# 1_PowerSupply.net
KiCad netlist of a schematic drawn in Altium Designer
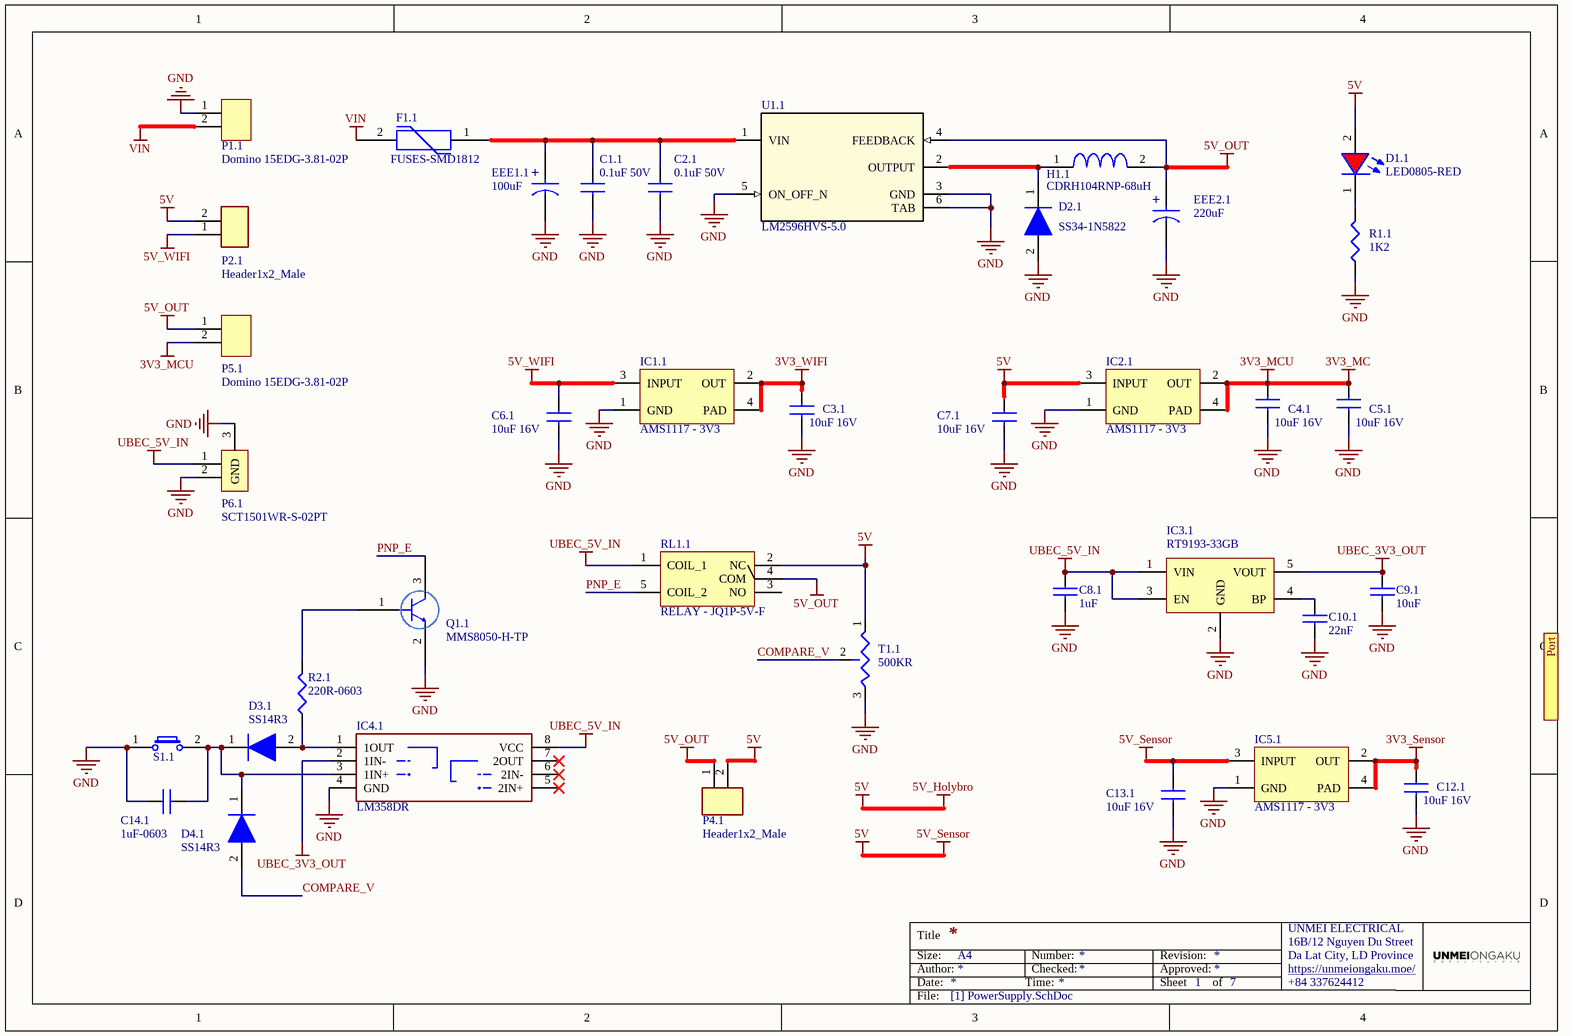
[diagram p0: [1] PowerSupply.SchDoc]

(export (version "E")
  (design (tool "Eeschema 10.0.6"))
  (components
    (comp (ref "C1.1")
      (value "0.1uF 50V")
      (footprint "CAP0805")
      (description "Cap Ceramic 0.1uF 50V X7R 10% SMD 2.0 x 1.2 mm 125 C Paper T/R")
      (fields
        (field (name "MANUFACTURER") "KEMET")
        (field (name "MANUFACTURER PART NUMBER") "C0805C104K5RACTU")
      )
      (libsource (lib "Minh_Lib") (part "C0805C104K5RACTU"))
    )
    (comp (ref "C2.1")
      (value "0.1uF 50V")
      (footprint "CAP0805")
      (description "Cap Ceramic 0.1uF 50V X7R 10% SMD 2.0 x 1.2 mm 125 C Paper T/R")
      (fields
        (field (name "MANUFACTURER") "KEMET")
        (field (name "MANUFACTURER PART NUMBER") "C0805C104K5RACTU")
      )
      (libsource (lib "Minh_Lib") (part "C0805C104K5RACTU"))
    )
    (comp (ref "C3.1")
      (value "10uF 16V")
      (footprint "CAP0805")
      (description "Ceramic Capacitors MLCC - SMD/SMT 16V 10uF X5R 0805 10%")
      (fields
        (field (name "MANUFACTURER") "KEMET")
        (field (name "MANUFACTURER PART NUMBER") "C0805C106K4PACTU")
      )
      (libsource (lib "Minh_Lib") (part "C0805C106K4PACTU"))
    )
    (comp (ref "C4.1")
      (value "10uF 16V")
      (footprint "CAP0805")
      (description "Ceramic Capacitors MLCC - SMD/SMT 16V 10uF X5R 0805 10%")
      (fields
        (field (name "MANUFACTURER") "KEMET")
        (field (name "MANUFACTURER PART NUMBER") "C0805C106K4PACTU")
      )
      (libsource (lib "Minh_Lib") (part "C0805C106K4PACTU"))
    )
    (comp (ref "C5.1")
      (value "10uF 16V")
      (footprint "CAP0805")
      (description "Ceramic Capacitors MLCC - SMD/SMT 16V 10uF X5R 0805 10%")
      (fields
        (field (name "MANUFACTURER") "KEMET")
        (field (name "MANUFACTURER PART NUMBER") "C0805C106K4PACTU")
      )
      (libsource (lib "Minh_Lib") (part "C0805C106K4PACTU"))
    )
    (comp (ref "C6.1")
      (value "10uF 16V")
      (footprint "CAP0805")
      (description "Ceramic Capacitors MLCC - SMD/SMT 16V 10uF X5R 0805 10%")
      (fields
        (field (name "MANUFACTURER") "KEMET")
        (field (name "MANUFACTURER PART NUMBER") "C0805C106K4PACTU")
      )
      (libsource (lib "Minh_Lib") (part "C0805C106K4PACTU"))
    )
    (comp (ref "C7.1")
      (value "10uF 16V")
      (footprint "CAP0805")
      (description "Ceramic Capacitors MLCC - SMD/SMT 16V 10uF X5R 0805 10%")
      (fields
        (field (name "MANUFACTURER") "KEMET")
        (field (name "MANUFACTURER PART NUMBER") "C0805C106K4PACTU")
      )
      (libsource (lib "Minh_Lib") (part "C0805C106K4PACTU"))
    )
    (comp (ref "C8.1")
      (value "1uF")
      (footprint "CAP0603")
      (description "CAP CER 1UF 16V X7R 0603")
      (fields (field (name "TOLERANCE") "±10%"))
      (libsource (lib "Minh_Lib") (part "CC0603KRX7R7BB105"))
    )
    (comp (ref "C9.1")
      (value "10uF")
      (footprint "CAP0603")
      (description "CAP CER 10UF 10V X5R 0603")
      (fields (field (name "TOLERANCE") "±10%"))
      (libsource (lib "Minh_Lib") (part "CC0603KRX5R6BB106"))
    )
    (comp (ref "C10.1")
      (value "22nF")
      (footprint "CAP0603")
      (description "Multilayer Ceramic Capacitors MLCC - SMD/SMT 22nF 50V X7R 10%")
      (fields
        (field (name "MANUFACTURER") "Yageo")
        (field (name "MANUFACTURER PART NUMBER") "CC0603KRX7R9BB223")
      )
      (libsource (lib "Minh_Lib") (part "CC0603KRX7R9BB223"))
    )
    (comp (ref "C12.1")
      (value "10uF 16V")
      (footprint "CAP0805")
      (description "Ceramic Capacitors MLCC - SMD/SMT 16V 10uF X5R 0805 10%")
      (fields
        (field (name "MANUFACTURER") "KEMET")
        (field (name "MANUFACTURER PART NUMBER") "C0805C106K4PACTU")
      )
      (libsource (lib "Minh_Lib") (part "C0805C106K4PACTU"))
    )
    (comp (ref "C13.1")
      (value "10uF 16V")
      (footprint "CAP0805")
      (description "Ceramic Capacitors MLCC - SMD/SMT 16V 10uF X5R 0805 10%")
      (fields
        (field (name "MANUFACTURER") "KEMET")
        (field (name "MANUFACTURER PART NUMBER") "C0805C106K4PACTU")
      )
      (libsource (lib "Minh_Lib") (part "C0805C106K4PACTU"))
    )
    (comp (ref "C14.1")
      (value "1uF-0603")
      (footprint "CAP0603")
      (description "CAP CER 1UF 16V X7R 0603")
      (fields (field (name "TOLERANCE") "±10%"))
      (libsource (lib "Minh_Lib") (part "CC0603KRX7R7BB105"))
    )
    (comp (ref "D1.1")
      (value "LED0805-RED")
      (footprint "LED0805-RED")
      (libsource (lib "Minh_Lib") (part "LED0805-RED"))
    )
    (comp (ref "D2.1")
      (value "SS34-1N5822")
      (footprint "SS34 - 1N5822 / DO-214AA, SMA")
      (description "SS Series 500 mV 3 A 40 V Max Reverse Voltage Schottky Rectifier - DO-214AB")
      (fields
        (field (name "MANUFACTURER") "ON Semiconductor / Fairchild")
        (field (name "MANUFACTURER PART NUMBER") "SS34")
      )
      (libsource (lib "Minh_Lib") (part "SS34"))
    )
    (comp (ref "D3.1")
      (value "SS14R3")
      (footprint "SS14 - 1N5819 / DO-214AA, SMA")
      (description "1A, 40V, Schottky Rectifier")
      (fields (field (name "MANUFACTURER") "Taiwan Semiconductor"))
      (libsource (lib "Minh_Lib") (part "SS14R3"))
    )
    (comp (ref "D4.1")
      (value "SS14R3")
      (footprint "SS14 - 1N5819 / DO-214AA, SMA")
      (description "1A, 40V, Schottky Rectifier")
      (fields (field (name "MANUFACTURER") "Taiwan Semiconductor"))
      (libsource (lib "Minh_Lib") (part "SS14R3"))
    )
    (comp (ref "EEE1.1")
      (value "100uF")
      (footprint "CAPACITOR/ALU - SIZE D8/SMD - 6.3X7.7")
      (description "Cap Aluminum 100uF 25V 20% (6.3 X 7.7mm) SMD 143mA 2000h 85°C T/R")
      (fields
        (field (name "MANUFACTURER") "Panasonic")
        (field (name "MANUFACTURER PART NUMBER") "EEE-1EA101XP")
      )
      (libsource (lib "Minh_Lib") (part "EEE-1EA101XP"))
    )
    (comp (ref "EEE2.1")
      (value "220uF")
      (footprint "CAPACITOR/ALU - SIZE D8/SMD - 6.3X7.7")
      (description "Cap Aluminum 100uF 25V 20% (6.3 X 7.7mm) SMD 143mA 2000h 85°C T/R")
      (fields
        (field (name "MANUFACTURER") "Panasonic")
        (field (name "MANUFACTURER PART NUMBER") "EEE-1EA101XP")
      )
      (libsource (lib "Minh_Lib") (part "EEE-1EA101XP"))
    )
    (comp (ref "F1.1")
      (value "FUSES-SMD1812")
      (footprint "FUSES - SMD1812")
      (libsource (lib "Minh_Lib") (part "FUSES-SMD1812"))
    )
    (comp (ref "H1.1")
      (value "CDRH104RNP-68uH")
      (footprint "CDRH104RNP")
      (description "Ind Power Shielded Wirewound 68uH 30% 100KHz Ferrite 1.42A Carrier T/R")
      (fields
        (field (name "MANUFACTURER") "Sumida")
        (field (name "MANUFACTURER PART NUMBER") "CDRH104RNP-680NC")
      )
      (libsource (lib "Minh_Lib") (part "CDRH104RNP-680NC"))
    )
    (comp (ref "IC1.1")
      (value "AMS1117 - 3V3")
      (footprint "SOT223-4M_AMS1117_3V3")
      (description "LDO Voltage Regulators 3.3V 1A Positive")
      (fields
        (field (name "MANUFACTURER") "ON Semiconductor")
        (field (name "MANUFACTURER PART NUMBER") "NCP1117ST33T3G")
      )
      (libsource (lib "Minh_Lib") (part "AMS1117 - 3V3"))
    )
    (comp (ref "IC2.1")
      (value "AMS1117 - 3V3")
      (footprint "SOT223-4M_AMS1117_3V3")
      (description "LDO Voltage Regulators 3.3V 1A Positive")
      (fields
        (field (name "MANUFACTURER") "ON Semiconductor")
        (field (name "MANUFACTURER PART NUMBER") "NCP1117ST33T3G")
      )
      (libsource (lib "Minh_Lib") (part "AMS1117 - 3V3"))
    )
    (comp (ref "IC3.1")
      (value "RT9193-33GB")
      (footprint "SOT23-5")
      (description "IC REG LDO 3.3V 0.3A SOT23-5")
      (libsource (lib "Minh_Lib") (part "RT9193-33GB"))
    )
    (comp (ref "IC4.1")
      (value "LM358DR")
      (footprint "SOP8")
      (description "IC OPAMP GP 700KHZ 8SOIC")
      (fields (field (name "MANUFACTURER") "Texas Instruments"))
      (libsource (lib "Minh_Lib") (part "LM358DR"))
    )
    (comp (ref "IC5.1")
      (value "AMS1117 - 3V3")
      (footprint "SOT223-4M_AMS1117_3V3")
      (description "LDO Voltage Regulators 3.3V 1A Positive")
      (fields
        (field (name "MANUFACTURER") "ON Semiconductor")
        (field (name "MANUFACTURER PART NUMBER") "NCP1117ST33T3G")
      )
      (libsource (lib "Minh_Lib") (part "AMS1117 - 3V3"))
    )
    (comp (ref "P1.1")
      (value "Domino 15EDG-3.81-02P")
      (footprint "Domino 15EDG3.81 2P")
      (libsource (lib "Minh_Lib") (part "Domino 15EDG-3.81-02P"))
    )
    (comp (ref "P2.1")
      (value "Header1x2_Male")
      (footprint "Minh_Lib:HDR1x2_2.54_MALE")
      (description "Header1x2_2.54_MALE")
      (libsource (lib "Minh_Lib") (part "HDR1x2_2.54_MALE"))
    )
    (comp (ref "P4.1")
      (value "Header1x2_Male")
      (footprint "Minh_Lib:HDR1x2_2.54_MALE")
      (description "Header1x2_2.54_MALE")
      (libsource (lib "") (part "HDR1x2_2.54_MALE_1"))
    )
    (comp (ref "P5.1")
      (value "Domino 15EDG-3.81-02P")
      (footprint "Domino 15EDG3.81 2P")
      (libsource (lib "Minh_Lib") (part "Domino 15EDG-3.81-02P"))
    )
    (comp (ref "P6.1")
      (value "SCT1501WR-S-02PT")
      (footprint "Connector ZH1.5 2P SMD")
      (libsource (lib "Minh_Lib") (part "SCT1501WR-S-02PT"))
    )
    (comp (ref "Q1.1")
      (value "MMS8050-H-TP")
      (footprint "SOT23")
      (description "Trans Gp Bjt NPN 25V 0.5A 3-PIN SOT-23 T/r")
      (fields (field (name "MANUFACTURER") "MCC"))
      (libsource (lib "Minh_Lib") (part "MMS8050-H-TP"))
    )
    (comp (ref "R1.1")
      (value "1K2")
      (footprint "RES0805")
      (description "贴片电阻 1.5KΩ ±5% 1/8W ±100ppm/℃ 0805")
      (fields
        (field (name "MANUFACTURER") "Yageo")
        (field (name "MANUFACTURER PART NUMBER") "RC0805JR-071K5L")
      )
      (libsource (lib "Minh_Lib") (part "RC0805JR-071K5L"))
    )
    (comp (ref "R2.1")
      (value "220R-0603")
      (footprint "RES0603 - 3D")
      (description "RES SMD 220 OHM 5% 1/10W 0603")
      (fields (field (name "TOLERANCE") "±5%"))
      (libsource (lib "Minh_Lib") (part "RC0603JR-07220RL"))
    )
    (comp (ref "RL1.1")
      (value "RELAY - JQ1P-5V-F")
      (footprint "RELAY - JQ1P - XV - F 10A SPDT")
      (description "RELAY GEN PURPOSE SPDT 10A 5V")
      (fields (field (name "MANUFACTURER") "Panasonic") (field (name "MANUFACTURER PART NUMBER") "JQ1P-5V-F"))
      (libsource (lib "Minh_Lib") (part "RELAY - JQ1P-5V-F"))
    )
    (comp (ref "S1.1")
      (value "434121043816")
      (footprint "Switches-6x3.5x4.3mm")
      (description "Switch Tactile Spst-no 0.05A 12V")
      (fields (field (name "MANUFACTURER") "Wurth Electronics"))
      (libsource (lib "Minh_Lib") (part "434121043816"))
    )
    (comp (ref "T1.1")
      (value "500KR")
      (footprint "Rheostat - 3296W")
      (fields
        (field (name "MANUFACTURER") "Bourns")
        (field (name "MANUFACTURER PART NUMBER") "3296W-1-504LF")
        (field (name "TOLERANCE") "10%")
      )
      (libsource (lib "Minh_Lib") (part "3296W-1-504LF"))
    )
    (comp (ref "U1.1")
      (value "LM2596HVS-5.0")
      (footprint "Minh_Lib:TO265-5")
      (description "Optoisolator 5KV Trans 4SMD / Optocoupler Dc-in 1-CH Transistor Dc-out 4-PIN PDIP SMD")
      (fields
        (field (name "MANUFACTURER_PART_NUMBER") "LM2596S-ADJ/NOPB")
        (field (name "PARTNUMBER") "LM2596SX-ADJ/NOPB")
        (field (name "COPYRIGHT") "Copyright (C) 2021 Ultra Librarian. All rights reserved.")
      )
      (libsource (lib "Minh_Lib") (part "LM2596S-ADJ/NOPB"))
    )
  )
  (nets
    (net (code "1") (name "/COMPARE_V") (class "Default")
      (node (ref "D4.1") (pin "2") (pintype "passive"))
      (node (ref "T1.1") (pin "2") (pinfunction "2_2") (pintype "passive"))
    )
    (net (code "2") (name "/PNP_E") (class "Default")
      (node (ref "Q1.1") (pin "3") (pinfunction "3_3") (pintype "passive"))
      (node (ref "RL1.1") (pin "5") (pinfunction "COIL_2_5") (pintype "passive"))
    )
    (net (code "4") (name "3V3_MC") (class "Default")
      (node (ref "C4.1") (pin "1") (pinfunction "1_1") (pintype "passive"))
      (node (ref "C5.1") (pin "1") (pinfunction "1_1") (pintype "passive"))
      (node (ref "IC2.1") (pin "2") (pinfunction "OUT_2") (pintype "passive"))
      (node (ref "IC2.1") (pin "4") (pinfunction "PAD_4") (pintype "passive"))
      (node (ref "P5.1") (pin "2") (pinfunction "2_2") (pintype "passive"))
    )
    (net (code "5") (name "3V3_Sensor") (class "Default")
      (node (ref "C12.1") (pin "1") (pinfunction "1_1") (pintype "passive"))
      (node (ref "IC5.1") (pin "2") (pinfunction "OUT_2") (pintype "passive"))
      (node (ref "IC5.1") (pin "4") (pinfunction "PAD_4") (pintype "passive"))
    )
    (net (code "6") (name "3V3_WIFI") (class "Default")
      (node (ref "C3.1") (pin "1") (pinfunction "1_1") (pintype "passive"))
      (node (ref "IC1.1") (pin "2") (pinfunction "OUT_2") (pintype "passive"))
      (node (ref "IC1.1") (pin "4") (pinfunction "PAD_4") (pintype "passive"))
    )
    (net (code "7") (name "5V") (class "Default")
      (node (ref "C13.1") (pin "1") (pinfunction "1_1") (pintype "passive"))
      (node (ref "C7.1") (pin "1") (pinfunction "1_1") (pintype "passive"))
      (node (ref "D1.1") (pin "2") (pinfunction "+_2") (pintype "passive"))
      (node (ref "IC2.1") (pin "3") (pinfunction "INPUT_3") (pintype "power_in"))
      (node (ref "IC5.1") (pin "3") (pinfunction "INPUT_3") (pintype "power_in"))
      (node (ref "P2.1") (pin "2") (pinfunction "2_2") (pintype "passive"))
      (node (ref "P4.1") (pin "2") (pinfunction "2_2") (pintype "passive"))
      (node (ref "RL1.1") (pin "2") (pinfunction "NC_2") (pintype "passive"))
      (node (ref "T1.1") (pin "1") (pinfunction "1_1") (pintype "passive"))
    )
    (net (code "8") (name "5V_OUT") (class "Default")
      (node (ref "EEE2.1") (pin "1") (pinfunction "1_1") (pintype "passive"))
      (node (ref "H1.1") (pin "2") (pinfunction "2_2") (pintype "passive"))
      (node (ref "P4.1") (pin "1") (pinfunction "1_1") (pintype "passive"))
      (node (ref "P5.1") (pin "1") (pinfunction "1_1") (pintype "passive"))
      (node (ref "RL1.1") (pin "4") (pinfunction "COM_4") (pintype "passive"))
      (node (ref "U1.1") (pin "4") (pinfunction "FEEDBACK_4") (pintype "input"))
    )
    (net (code "9") (name "5V_WIFI") (class "Default")
      (node (ref "C6.1") (pin "1") (pinfunction "1_1") (pintype "passive"))
      (node (ref "IC1.1") (pin "3") (pinfunction "INPUT_3") (pintype "power_in"))
      (node (ref "P2.1") (pin "1") (pinfunction "1_1") (pintype "passive"))
    )
    (net (code "10") (name "GND") (class "Default")
      (node (ref "C1.1") (pin "2") (pinfunction "2_2") (pintype "passive"))
      (node (ref "C10.1") (pin "2") (pinfunction "2_2") (pintype "passive"))
      (node (ref "C12.1") (pin "2") (pinfunction "2_2") (pintype "passive"))
      (node (ref "C13.1") (pin "2") (pinfunction "2_2") (pintype "passive"))
      (node (ref "C14.1") (pin "1") (pinfunction "1_1") (pintype "passive"))
      (node (ref "C2.1") (pin "2") (pinfunction "2_2") (pintype "passive"))
      (node (ref "C3.1") (pin "2") (pinfunction "2_2") (pintype "passive"))
      (node (ref "C4.1") (pin "2") (pinfunction "2_2") (pintype "passive"))
      (node (ref "C5.1") (pin "2") (pinfunction "2_2") (pintype "passive"))
      (node (ref "C6.1") (pin "2") (pinfunction "2_2") (pintype "passive"))
      (node (ref "C7.1") (pin "2") (pinfunction "2_2") (pintype "passive"))
      (node (ref "C8.1") (pin "2") (pinfunction "2_2") (pintype "passive"))
      (node (ref "C9.1") (pin "2") (pinfunction "2_2") (pintype "passive"))
      (node (ref "D2.1") (pin "2") (pintype "passive"))
      (node (ref "EEE1.1") (pin "2") (pinfunction "2_2") (pintype "passive"))
      (node (ref "EEE2.1") (pin "2") (pinfunction "2_2") (pintype "passive"))
      (node (ref "IC1.1") (pin "1") (pinfunction "GND_1") (pintype "power_in"))
      (node (ref "IC2.1") (pin "1") (pinfunction "GND_1") (pintype "power_in"))
      (node (ref "IC3.1") (pin "2") (pinfunction "GND_2") (pintype "passive"))
      (node (ref "IC4.1") (pin "4") (pinfunction "GND_4") (pintype "passive"))
      (node (ref "IC5.1") (pin "1") (pinfunction "GND_1") (pintype "power_in"))
      (node (ref "P1.1") (pin "1") (pinfunction "1_1") (pintype "passive"))
      (node (ref "P6.1") (pin "2") (pinfunction "2_2") (pintype "passive"))
      (node (ref "P6.1") (pin "3") (pinfunction "GND_3") (pintype "passive"))
      (node (ref "Q1.1") (pin "2") (pinfunction "2_2") (pintype "passive"))
      (node (ref "R1.1") (pin "1") (pinfunction "1_1") (pintype "passive"))
      (node (ref "S1.1") (pin "1") (pinfunction "1_1") (pintype "passive"))
      (node (ref "T1.1") (pin "3") (pinfunction "3_3") (pintype "passive"))
      (node (ref "U1.1") (pin "3") (pinfunction "GND_3") (pintype "power_in"))
      (node (ref "U1.1") (pin "5") (pinfunction "ON_OFF_N_5") (pintype "input"))
      (node (ref "U1.1") (pin "6") (pinfunction "TAB_6") (pintype "power_in"))
    )
    (net (code "11") (name "Net-(D1.1-+-Pad1)") (class "Default")
      (node (ref "D1.1") (pin "1") (pinfunction "+_1") (pintype "passive"))
      (node (ref "R1.1") (pin "2") (pinfunction "2_2") (pintype "passive"))
    )
    (net (code "12") (name "Net-(F1.1-0)") (class "Default")
      (node (ref "C1.1") (pin "1") (pinfunction "1_1") (pintype "passive"))
      (node (ref "C2.1") (pin "1") (pinfunction "1_1") (pintype "passive"))
      (node (ref "EEE1.1") (pin "1") (pinfunction "1_1") (pintype "passive"))
      (node (ref "F1.1") (pin "1") (pinfunction "0_1") (pintype "passive"))
      (node (ref "U1.1") (pin "1") (pinfunction "VIN_1") (pintype "power_in"))
    )
    (net (code "13") (name "Net-(IC3.1-BP)") (class "Default")
      (node (ref "C10.1") (pin "1") (pinfunction "1_1") (pintype "passive"))
      (node (ref "IC3.1") (pin "4") (pinfunction "BP_4") (pintype "passive"))
    )
    (net (code "14") (name "Net-(IC4.1-1IN+)") (class "Default")
      (node (ref "C14.1") (pin "2") (pinfunction "2_2") (pintype "passive"))
      (node (ref "D3.1") (pin "1") (pintype "passive"))
      (node (ref "D4.1") (pin "1") (pintype "passive"))
      (node (ref "IC4.1") (pin "3") (pinfunction "1IN+_3") (pintype "passive"))
      (node (ref "S1.1") (pin "2") (pinfunction "2_2") (pintype "passive"))
    )
    (net (code "15") (name "Net-(IC4.1-1OUT)") (class "Default")
      (node (ref "D3.1") (pin "2") (pintype "passive"))
      (node (ref "IC4.1") (pin "1") (pinfunction "1OUT_1") (pintype "passive"))
      (node (ref "R2.1") (pin "1") (pinfunction "1_1") (pintype "passive"))
    )
    (net (code "16") (name "Net-(Q1.1-Pad1)") (class "Default")
      (node (ref "Q1.1") (pin "1") (pinfunction "1_1") (pintype "passive"))
      (node (ref "R2.1") (pin "2") (pinfunction "2_2") (pintype "passive"))
    )
    (net (code "17") (name "Net-(U1.1-OUTPUT)") (class "Default")
      (node (ref "D2.1") (pin "1") (pintype "passive"))
      (node (ref "H1.1") (pin "1") (pinfunction "1_1") (pintype "passive"))
      (node (ref "U1.1") (pin "2") (pinfunction "OUTPUT_2") (pintype "power_in"))
    )
    (net (code "18") (name "UBEC_3V3_OUT") (class "Default")
      (node (ref "C9.1") (pin "1") (pinfunction "1_1") (pintype "passive"))
      (node (ref "IC3.1") (pin "5") (pinfunction "VOUT_5") (pintype "power_in"))
      (node (ref "IC4.1") (pin "2") (pinfunction "1IN-_2") (pintype "passive"))
    )
    (net (code "19") (name "UBEC_5V_IN") (class "Default")
      (node (ref "C8.1") (pin "1") (pinfunction "1_1") (pintype "passive"))
      (node (ref "IC3.1") (pin "1") (pinfunction "VIN_1") (pintype "power_in"))
      (node (ref "IC3.1") (pin "3") (pinfunction "EN_3") (pintype "passive"))
      (node (ref "IC4.1") (pin "8") (pinfunction "VCC_8") (pintype "passive"))
      (node (ref "P6.1") (pin "1") (pinfunction "1_1") (pintype "passive"))
      (node (ref "RL1.1") (pin "1") (pinfunction "COIL_1_1") (pintype "passive"))
    )
    (net (code "20") (name "VIN") (class "Default")
      (node (ref "F1.1") (pin "2") (pinfunction "1_2") (pintype "passive"))
      (node (ref "P1.1") (pin "2") (pinfunction "2_2") (pintype "passive"))
    )
    (net (code "21") (name "unconnected-(IC4.1-2IN+-Pad5)") (class "Default")
      (node (ref "IC4.1") (pin "5") (pinfunction "2IN+_5") (pintype "passive+no_connect"))
    )
    (net (code "22") (name "unconnected-(IC4.1-2IN--Pad6)") (class "Default")
      (node (ref "IC4.1") (pin "6") (pinfunction "2IN-_6") (pintype "passive+no_connect"))
    )
    (net (code "23") (name "unconnected-(IC4.1-2OUT-Pad7)") (class "Default")
      (node (ref "IC4.1") (pin "7") (pinfunction "2OUT_7") (pintype "passive+no_connect"))
    )
    (net (code "24") (name "unconnected-(RL1.1-NO-Pad3)") (class "Default")
      (node (ref "RL1.1") (pin "3") (pinfunction "NO_3") (pintype "passive"))
    )
  )
)
